# volt_sense.net
KiCad netlist of a schematic drawn in Altium Designer
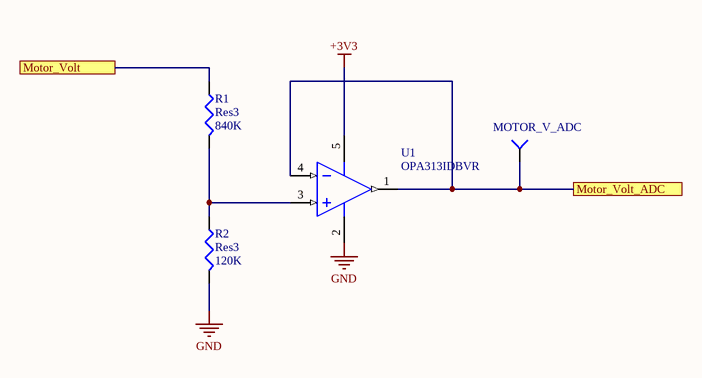
[diagram p0: volt_sense.SchDoc]

(export (version "E")
  (design (tool "Eeschema 10.0.6"))
  (components
    (comp (ref "R1")
      (value "Res3")
      (footprint "J1-0603")
      (description "Resistor")
      (fields (field (name "ALTIUM_VALUE") "840K") (field (name "PUBLISHER") "Altium Limited"))
      (libsource (lib "Miscellaneous Devices") (part "Res3"))
    )
    (comp (ref "R2")
      (value "Res3")
      (footprint "J1-0603")
      (description "Resistor")
      (fields (field (name "ALTIUM_VALUE") "120K") (field (name "PUBLISHER") "Altium Limited"))
      (libsource (lib "Miscellaneous Devices") (part "Res3"))
    )
    (comp (ref "TP_Motor_V")
      (value "MOTOR_V_ADC")
      (footprint "TESTPOINT")
      (description "TESTPOINT_SMD")
      (libsource (lib "UWRT_Schematic_Library_2020") (part "TESTPOINT_SMD"))
    )
    (comp (ref "U1")
      (value "OPA313IDBVR")
      (footprint "DBV0005A_M")
      (fields
        (field (name "MANUFACTURER") "Texas Instruments")
        (field (name "DIGI-KEY PART NUMBER") "296-35607-1-ND")
      )
      (libsource (lib "UWRT_Schematic_Library_2020") (part "OPAMP"))
    )
  )
  (nets
    (net (code "1") (name "+3V3") (class "Default")
      (node (ref "U1") (pin "5") (pinfunction "V+_5") (pintype "power_in"))
    )
    (net (code "2") (name "/Motor_Volt") (class "Default")
      (node (ref "R1") (pin "1") (pinfunction "1_1") (pintype "passive"))
    )
    (net (code "3") (name "/Motor_Volt_ADC") (class "Default")
      (node (ref "TP_Motor_V") (pin "1") (pinfunction "=value_1") (pintype "passive"))
      (node (ref "U1") (pin "1") (pinfunction "OUT_1") (pintype "output"))
      (node (ref "U1") (pin "4") (pinfunction "IN-_4") (pintype "input"))
    )
    (net (code "4") (name "GND") (class "Default")
      (node (ref "R2") (pin "2") (pinfunction "2_2") (pintype "passive"))
      (node (ref "U1") (pin "2") (pinfunction "V-_2") (pintype "power_in"))
    )
    (net (code "5") (name "Net-(U1-IN+)") (class "Default")
      (node (ref "R1") (pin "2") (pinfunction "2_2") (pintype "passive"))
      (node (ref "R2") (pin "1") (pinfunction "1_1") (pintype "passive"))
      (node (ref "U1") (pin "3") (pinfunction "IN+_3") (pintype "input"))
    )
  )
)
